# control_and_power.net
KiCad netlist of a schematic drawn in Altium Designer
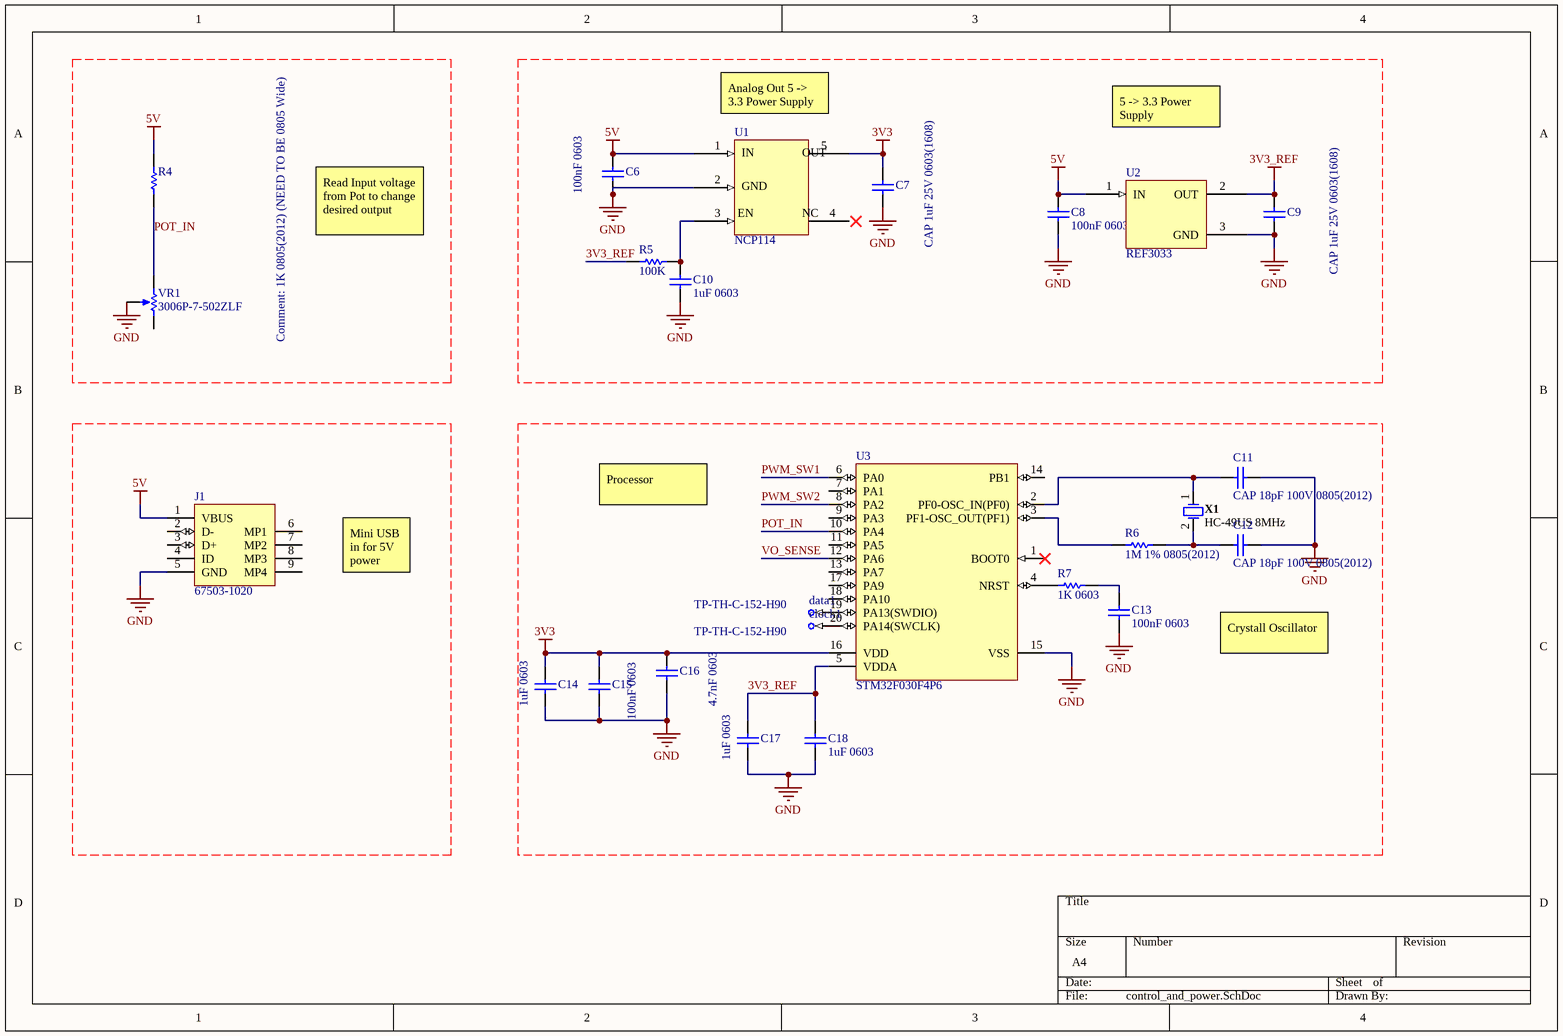
[diagram p0: control_and_power.SchDoc]

(export (version "E")
  (design (tool "Eeschema 10.0.6"))
  (components
    (comp (ref "C6")
      (value "100nF 0603")
      (footprint "CAPC0603(1608)100_M")
      (description "CAP 1uF 25V -20% to +80% 0603 (1608 Metric) Thickness 1mm SMD")
      (fields (field (name "TOLERANCE") "-20% to +80%"))
      (libsource (lib "Altium Content Vault") (part "CMP-1035-02742-1"))
    )
    (comp (ref "C7")
      (value "CAP 1uF 25V 0603(1608)")
      (footprint "CAPC0603(1608)100_M")
      (description "CAP 1uF 25V -20% to +80% 0603 (1608 Metric) Thickness 1mm SMD")
      (fields (field (name "TOLERANCE") "-20% to +80%"))
      (libsource (lib "Altium Content Vault") (part "CAP"))
    )
    (comp (ref "C8")
      (value "100nF 0603")
      (footprint "CAPC0603(1608)100_M")
      (description "CAP 1uF 25V -20% to +80% 0603 (1608 Metric) Thickness 1mm SMD")
      (fields (field (name "TOLERANCE") "-20% to +80%"))
      (libsource (lib "Altium Content Vault") (part "CMP-1035-02742-1"))
    )
    (comp (ref "C9")
      (value "CAP 1uF 25V 0603(1608)")
      (footprint "CAPC0603(1608)100_M")
      (description "CAP 1uF 25V -20% to +80% 0603 (1608 Metric) Thickness 1mm SMD")
      (fields (field (name "TOLERANCE") "-20% to +80%"))
      (libsource (lib "Altium Content Vault") (part "CAP"))
    )
    (comp (ref "C10")
      (value "1uF 0603")
      (footprint "CAPC0603(1608)100_M")
      (description "CAP 1uF 25V -20% to +80% 0603 (1608 Metric) Thickness 1mm SMD")
      (fields (field (name "TOLERANCE") "-20% to +80%"))
      (libsource (lib "Altium Content Vault") (part "CMP-1035-02742-1"))
    )
    (comp (ref "C11")
      (value "CAP 18pF 100V 0805(2012)")
      (footprint "CAPC0805(2012)145_M")
      (description "CAP 18pF 100V ±10% 0805 (2012 Metric) Thickness 1.45mm SMD")
      (fields (field (name "TOLERANCE") "Â±10%"))
      (libsource (lib "Altium Content Vault") (part "CMP-1036-01160-1"))
    )
    (comp (ref "C12")
      (value "CAP 18pF 100V 0805(2012)")
      (footprint "CAPC0805(2012)145_M")
      (description "CAP 18pF 100V ±10% 0805 (2012 Metric) Thickness 1.45mm SMD")
      (fields (field (name "TOLERANCE") "Â±10%"))
      (libsource (lib "Altium Content Vault") (part "CMP-1036-01160-1"))
    )
    (comp (ref "C13")
      (value "100nF 0603")
      (footprint "CAPC0603(1608)100_M")
      (description "CAP 1uF 25V -20% to +80% 0603 (1608 Metric) Thickness 1mm SMD")
      (fields (field (name "TOLERANCE") "-20% to +80%"))
      (libsource (lib "Altium Content Vault") (part "CMP-1035-02742-1"))
    )
    (comp (ref "C14")
      (value "1uF 0603")
      (footprint "CAPC0603(1608)100_M")
      (description "CAP 1uF 25V -20% to +80% 0603 (1608 Metric) Thickness 1mm SMD")
      (fields (field (name "TOLERANCE") "-20% to +80%"))
      (libsource (lib "Altium Content Vault") (part "CMP-1035-02742-1"))
    )
    (comp (ref "C15")
      (value "100nF 0603")
      (footprint "CAPC0603(1608)100_M")
      (description "CAP 1uF 25V -20% to +80% 0603 (1608 Metric) Thickness 1mm SMD")
      (fields (field (name "TOLERANCE") "-20% to +80%"))
      (libsource (lib "Altium Content Vault") (part "CMP-1035-02742-1"))
    )
    (comp (ref "C16")
      (value "4.7nF 0603")
      (footprint "CAPC0603(1608)100_M")
      (description "CAP 1uF 25V -20% to +80% 0603 (1608 Metric) Thickness 1mm SMD")
      (fields (field (name "TOLERANCE") "-20% to +80%"))
      (libsource (lib "Altium Content Vault") (part "CMP-1035-02742-1"))
    )
    (comp (ref "C17")
      (value "1uF 0603")
      (footprint "CAPC0603(1608)100_M")
      (description "CAP 1uF 25V -20% to +80% 0603 (1608 Metric) Thickness 1mm SMD")
      (fields (field (name "TOLERANCE") "-20% to +80%"))
      (libsource (lib "Altium Content Vault") (part "CMP-1035-02742-1"))
    )
    (comp (ref "C18")
      (value "1uF 0603")
      (footprint "CAPC0603(1608)100_M")
      (description "CAP 1uF 25V -20% to +80% 0603 (1608 Metric) Thickness 1mm SMD")
      (fields (field (name "TOLERANCE") "-20% to +80%"))
      (libsource (lib "Altium Content Vault") (part "CMP-1035-02742-1"))
    )
    (comp (ref "clock1")
      (value "TP-TH-C-152-H90")
      (footprint "TP-TH-C-152-H90")
      (description "Test Point, Through Hole, Hole Size 0.9 mm, PCB Mount with Silkscreen Box")
      (fields (field (name "MANUFACTURER") "No Vendor"))
      (libsource (lib "Altium Content Vault") (part "TP-TH"))
    )
    (comp (ref "data1")
      (value "TP-TH-C-152-H90")
      (footprint "TP-TH-C-152-H90")
      (description "Test Point, Through Hole, Hole Size 0.9 mm, PCB Mount with Silkscreen Box")
      (fields (field (name "MANUFACTURER") "No Vendor"))
      (libsource (lib "Altium Content Vault") (part "TP-TH"))
    )
    (comp (ref "J1")
      (value "67503-1020")
      (footprint "MOLX-67503-1020_V")
      (description "USB, MINI, SMD, RA KME04-USBMU03A01")
      (fields (field (name "MANUFACTURER") "Molex"))
      (libsource (lib "Altium Content Vault") (part "MOLX-67503-1020"))
    )
    (comp (ref "R4")
      (value "1K 0805(2012) (NEED TO BE 0805 Wide)")
      (footprint "RESC0805(2012)_N")
      (description "30R 0.125W 5% 0805 (2012 Metric)  SMD")
      (fields (field (name "POWER") "0.125 W") (field (name "TOLERANCE") "5 %"))
      (libsource (lib "Altium Content Vault") (part "RES"))
    )
    (comp (ref "R5")
      (value "100K")
      (footprint "RESC0603(1608)_N")
      (description "2K 0.1W 1% 0603 (1608 Metric)  SMD")
      (fields (field (name "POWER") "0.1 W") (field (name "TOLERANCE") "1 %"))
      (libsource (lib "Altium Content Vault") (part "CMP-1012-00542-1"))
    )
    (comp (ref "R6")
      (value "1M 1% 0805(2012)")
      (footprint "RESC0805(2012)_N")
      (description "1M 0.125W 1% 0805 (2012 Metric)  SMD")
      (fields (field (name "POWER") "0.125 W") (field (name "TOLERANCE") "1 %"))
      (libsource (lib "Altium Content Vault") (part "RES"))
    )
    (comp (ref "R7")
      (value "1K 0603")
      (footprint "RESC0603(1608)_N")
      (description "2K 0.1W 1% 0603 (1608 Metric)  SMD")
      (fields (field (name "POWER") "0.1 W") (field (name "TOLERANCE") "1 %"))
      (libsource (lib "Altium Content Vault") (part "CMP-1012-00542-1"))
    )
    (comp (ref "U1") (value "NCP114") (footprint "SOT23-5_N") (libsource (lib "Schlib1") (part "NCP114")))
    (comp (ref "U2") (value "REF3033") (footprint "SOT23-3") (libsource (lib "Schlib1") (part "REF3033")))
    (comp (ref "U3")
      (value "STM32F030F4P6")
      (footprint "STM-TSSOP20_L")
      (libsource (lib "Altium Content Vault") (part "MC-ARM-STM32F030-IL20"))
    )
    (comp (ref "VR1")
      (value "3006P-7-502ZLF")
      (footprint "BOUR-3006P-3_V")
      (fields (field (name "MANUFACTURER") "Bourns"))
      (libsource (lib "Altium Content Vault") (part "BOUR-3006P-3"))
    )
    (comp (ref "X1")
      (value "HC-49US 8MHz")
      (footprint "JPY-HC-49US")
      (description "Crystal, 16 MHz, +/- 30 ppm, 18 pF, -20 to 70 degC, 2-Pin THD")
      (fields (field (name "MANUFACTURER") "Jing peng yuan"))
      (libsource (lib "Altium Content Vault") (part "XTAL-1-2-2"))
    )
  )
  (nets
    (net (code "1") (name "/POT_IN") (class "Default")
      (node (ref "R4") (pin "1") (pinfunction "1_1") (pintype "passive"))
      (node (ref "U3") (pin "10") (pinfunction "PA4_10") (pintype "bidirectional"))
      (node (ref "VR1") (pin "3") (pinfunction "CW_3") (pintype "passive"))
    )
    (net (code "2") (name "/PWM_SW1") (class "Default")
      (node (ref "U3") (pin "6") (pinfunction "PA0_6") (pintype "bidirectional"))
    )
    (net (code "3") (name "/PWM_SW2") (class "Default")
      (node (ref "U3") (pin "8") (pinfunction "PA2_8") (pintype "bidirectional"))
    )
    (net (code "4") (name "/VO_SENSE") (class "Default")
      (node (ref "U3") (pin "12") (pinfunction "PA6_12") (pintype "bidirectional"))
    )
    (net (code "5") (name "3V3") (class "Default")
      (node (ref "C14") (pin "2") (pinfunction "2_2") (pintype "passive"))
      (node (ref "C15") (pin "2") (pinfunction "2_2") (pintype "passive"))
      (node (ref "C16") (pin "2") (pinfunction "2_2") (pintype "passive"))
      (node (ref "C7") (pin "2") (pinfunction "2_2") (pintype "passive"))
      (node (ref "U1") (pin "5") (pinfunction "OUT_5") (pintype "power_in"))
      (node (ref "U3") (pin "16") (pinfunction "VDD_16") (pintype "power_in"))
    )
    (net (code "6") (name "3V3_REF") (class "Default")
      (node (ref "C17") (pin "2") (pinfunction "2_2") (pintype "passive"))
      (node (ref "C18") (pin "2") (pinfunction "2_2") (pintype "passive"))
      (node (ref "C9") (pin "2") (pinfunction "2_2") (pintype "passive"))
      (node (ref "R5") (pin "1") (pinfunction "1_1") (pintype "passive"))
      (node (ref "U2") (pin "2") (pinfunction "OUT_2") (pintype "power_in"))
      (node (ref "U3") (pin "5") (pinfunction "VDDA_5") (pintype "power_in"))
    )
    (net (code "7") (name "5V") (class "Default")
      (node (ref "C6") (pin "2") (pinfunction "2_2") (pintype "passive"))
      (node (ref "C8") (pin "2") (pinfunction "2_2") (pintype "passive"))
      (node (ref "J1") (pin "1") (pinfunction "VBUS_1") (pintype "power_in"))
      (node (ref "R4") (pin "2") (pinfunction "2_2") (pintype "passive"))
      (node (ref "U1") (pin "1") (pinfunction "IN_1") (pintype "input"))
      (node (ref "U2") (pin "1") (pinfunction "IN_1") (pintype "input"))
    )
    (net (code "8") (name "GND") (class "Default")
      (node (ref "C10") (pin "1") (pinfunction "1_1") (pintype "passive"))
      (node (ref "C11") (pin "2") (pinfunction "2_2") (pintype "passive"))
      (node (ref "C12") (pin "2") (pinfunction "2_2") (pintype "passive"))
      (node (ref "C13") (pin "1") (pinfunction "1_1") (pintype "passive"))
      (node (ref "C14") (pin "1") (pinfunction "1_1") (pintype "passive"))
      (node (ref "C15") (pin "1") (pinfunction "1_1") (pintype "passive"))
      (node (ref "C16") (pin "1") (pinfunction "1_1") (pintype "passive"))
      (node (ref "C17") (pin "1") (pinfunction "1_1") (pintype "passive"))
      (node (ref "C18") (pin "1") (pinfunction "1_1") (pintype "passive"))
      (node (ref "C6") (pin "1") (pinfunction "1_1") (pintype "passive"))
      (node (ref "C7") (pin "1") (pinfunction "1_1") (pintype "passive"))
      (node (ref "C8") (pin "1") (pinfunction "1_1") (pintype "passive"))
      (node (ref "C9") (pin "1") (pinfunction "1_1") (pintype "passive"))
      (node (ref "J1") (pin "5") (pinfunction "GND_5") (pintype "power_in"))
      (node (ref "U1") (pin "2") (pinfunction "GND_2") (pintype "input"))
      (node (ref "U2") (pin "3") (pinfunction "GND_3") (pintype "passive"))
      (node (ref "U3") (pin "15") (pinfunction "VSS_15") (pintype "power_in"))
      (node (ref "VR1") (pin "2") (pinfunction "WIPER_2") (pintype "passive"))
    )
    (net (code "9") (name "Net-(C12-Pad1)") (class "Default")
      (node (ref "C12") (pin "1") (pinfunction "1_1") (pintype "passive"))
      (node (ref "R6") (pin "2") (pinfunction "2_2") (pintype "passive"))
      (node (ref "X1") (pin "2") (pinfunction "2_2") (pintype "passive"))
    )
    (net (code "10") (name "Net-(C13-Pad2)") (class "Default")
      (node (ref "C13") (pin "2") (pinfunction "2_2") (pintype "passive"))
      (node (ref "R7") (pin "2") (pinfunction "2_2") (pintype "passive"))
    )
    (net (code "11") (name "Net-(U1-EN)") (class "Default")
      (node (ref "C10") (pin "2") (pinfunction "2_2") (pintype "passive"))
      (node (ref "R5") (pin "2") (pinfunction "2_2") (pintype "passive"))
      (node (ref "U1") (pin "3") (pinfunction "EN_3") (pintype "input"))
    )
    (net (code "12") (name "Net-(U3-NRST)") (class "Default")
      (node (ref "R7") (pin "1") (pinfunction "1_1") (pintype "passive"))
      (node (ref "U3") (pin "4") (pinfunction "NRST_4") (pintype "bidirectional"))
    )
    (net (code "13") (name "Net-(U3-PA13(SWDIO))") (class "Default")
      (node (ref "U3") (pin "19") (pinfunction "PA13(SWDIO)_19") (pintype "bidirectional"))
      (node (ref "data1") (pin "1") (pinfunction "1_1") (pintype "input"))
    )
    (net (code "14") (name "Net-(U3-PA14(SWCLK))") (class "Default")
      (node (ref "U3") (pin "20") (pinfunction "PA14(SWCLK)_20") (pintype "bidirectional"))
      (node (ref "clock1") (pin "1") (pinfunction "1_1") (pintype "input"))
    )
    (net (code "15") (name "Net-(U3-PF0-OSC_IN(PF0))") (class "Default")
      (node (ref "C11") (pin "1") (pinfunction "1_1") (pintype "passive"))
      (node (ref "U3") (pin "2") (pinfunction "PF0-OSC_IN(PF0)_2") (pintype "bidirectional"))
      (node (ref "X1") (pin "1") (pinfunction "1_1") (pintype "passive"))
    )
    (net (code "16") (name "Net-(U3-PF1-OSC_OUT(PF1))") (class "Default")
      (node (ref "R6") (pin "1") (pinfunction "1_1") (pintype "passive"))
      (node (ref "U3") (pin "3") (pinfunction "PF1-OSC_OUT(PF1)_3") (pintype "bidirectional"))
    )
    (net (code "17") (name "unconnected-(J1-D+-Pad3)") (class "Default")
      (node (ref "J1") (pin "3") (pinfunction "D+_3") (pintype "bidirectional"))
    )
    (net (code "18") (name "unconnected-(J1-D--Pad2)") (class "Default")
      (node (ref "J1") (pin "2") (pinfunction "D-_2") (pintype "bidirectional"))
    )
    (net (code "19") (name "unconnected-(J1-ID-Pad4)") (class "Default")
      (node (ref "J1") (pin "4") (pinfunction "ID_4") (pintype "passive"))
    )
    (net (code "20") (name "unconnected-(J1-MP1-Pad6)") (class "Default")
      (node (ref "J1") (pin "6") (pinfunction "MP1_6") (pintype "passive"))
    )
    (net (code "21") (name "unconnected-(J1-MP2-Pad7)") (class "Default")
      (node (ref "J1") (pin "7") (pinfunction "MP2_7") (pintype "passive"))
    )
    (net (code "22") (name "unconnected-(J1-MP3-Pad8)") (class "Default")
      (node (ref "J1") (pin "8") (pinfunction "MP3_8") (pintype "passive"))
    )
    (net (code "23") (name "unconnected-(J1-MP4-Pad9)") (class "Default")
      (node (ref "J1") (pin "9") (pinfunction "MP4_9") (pintype "passive"))
    )
    (net (code "24") (name "unconnected-(U1-NC-Pad4)") (class "Default")
      (node (ref "U1") (pin "4") (pinfunction "NC_4") (pintype "passive"))
    )
    (net (code "25") (name "unconnected-(U3-BOOT0-Pad1)") (class "Default")
      (node (ref "U3") (pin "1") (pinfunction "BOOT0_1") (pintype "input+no_connect"))
    )
    (net (code "26") (name "unconnected-(U3-PA1-Pad7)") (class "Default")
      (node (ref "U3") (pin "7") (pinfunction "PA1_7") (pintype "bidirectional"))
    )
    (net (code "27") (name "unconnected-(U3-PA3-Pad9)") (class "Default")
      (node (ref "U3") (pin "9") (pinfunction "PA3_9") (pintype "bidirectional"))
    )
    (net (code "28") (name "unconnected-(U3-PA5-Pad11)") (class "Default")
      (node (ref "U3") (pin "11") (pinfunction "PA5_11") (pintype "bidirectional"))
    )
    (net (code "29") (name "unconnected-(U3-PA7-Pad13)") (class "Default")
      (node (ref "U3") (pin "13") (pinfunction "PA7_13") (pintype "bidirectional"))
    )
    (net (code "30") (name "unconnected-(U3-PA9-Pad17)") (class "Default")
      (node (ref "U3") (pin "17") (pinfunction "PA9_17") (pintype "bidirectional"))
    )
    (net (code "31") (name "unconnected-(U3-PA10-Pad18)") (class "Default")
      (node (ref "U3") (pin "18") (pinfunction "PA10_18") (pintype "bidirectional"))
    )
    (net (code "32") (name "unconnected-(U3-PB1-Pad14)") (class "Default")
      (node (ref "U3") (pin "14") (pinfunction "PB1_14") (pintype "bidirectional"))
    )
    (net (code "33") (name "unconnected-(VR1-CCW-Pad1)") (class "Default")
      (node (ref "VR1") (pin "1") (pinfunction "CCW_1") (pintype "passive"))
    )
  )
)
